# easyeda_source_code.net
KiCad netlist of a schematic drawn in EasyEDA
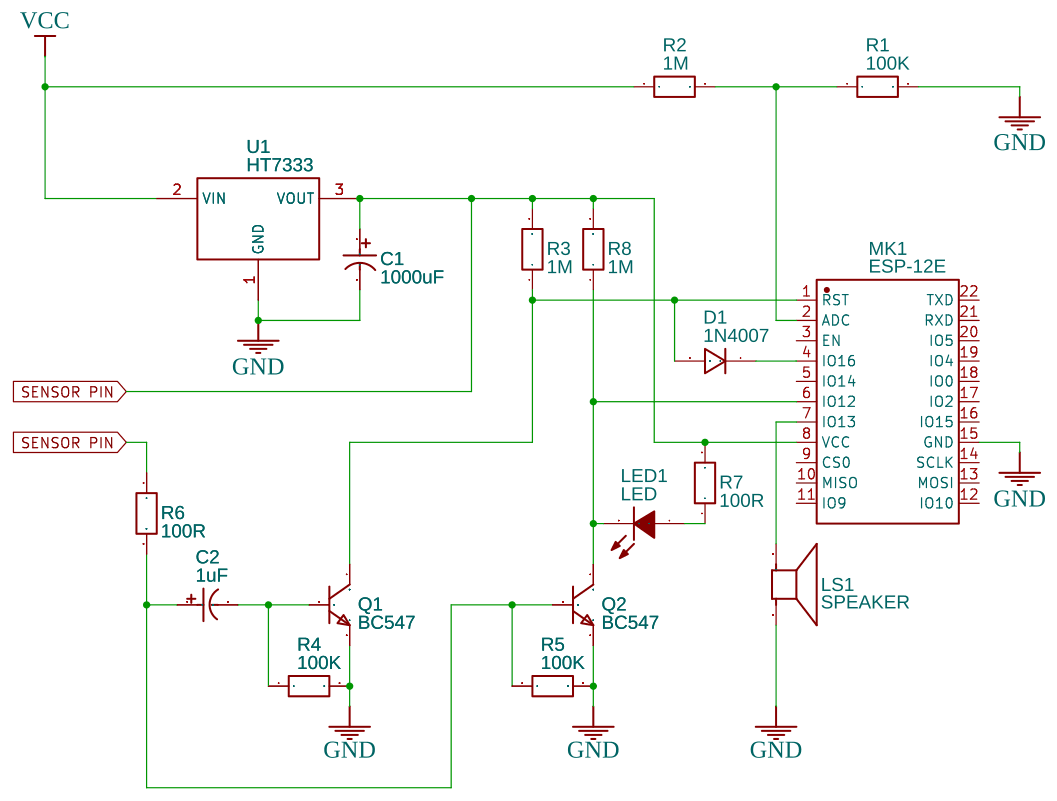
[diagram p0: schematic sheet]

(export (version "E")
  (design (tool "Eeschema 10.0.6"))
  (components
    (comp (ref "C1")
      (value "1000uF")
      (fields
        (field (name "BOM_Manufacturer Part") "1000uF 10V绿金 10*15")
        (field (name "BOM_Supplier Part") "C43339")
      )
      (libsource (lib "") (part "1000uF 10V 10*15"))
    )
    (comp (ref "C2")
      (value "1uF")
      (fields
        (field (name "BOM_Manufacturer Part") "1000uF 10V绿金 10*15")
        (field (name "BOM_Supplier Part") "C43339")
      )
      (libsource (lib "") (part "1000uF 10V 10*15_1"))
    )
    (comp (ref "D1")
      (value "1N4007")
      (fields (field (name "BOM_Manufacturer Part") "1N4007W") (field (name "BOM_Supplier Part") "C328592"))
      (libsource (lib "") (part "1N4007W"))
    )
    (comp (ref "LED1")
      (value "LED")
      (fields
        (field (name "BOM_Manufacturer Part") "19-217/R6C-AL1M2VY/3T")
        (field (name "BOM_Supplier Part") "C72044")
      )
      (libsource (lib "") (part "LED-0603_R"))
    )
    (comp (ref "LS1") (value "SPEAKER") (libsource (lib "") (part "SPEAKERPS12")))
    (comp (ref "MK1")
      (value "ESP-12E")
      (fields (field (name "BOM_Supplier Part") "C89297"))
      (libsource (lib "") (part "ESP-12E"))
    )
    (comp (ref "Q1")
      (value "BC547")
      (fields (field (name "BOM_Manufacturer Part") "BC547BTA") (field (name "BOM_Supplier Part") "C258144"))
      (libsource (lib "") (part "BC547BTA"))
    )
    (comp (ref "Q2")
      (value "BC547")
      (fields (field (name "BOM_Manufacturer Part") "BC547BTA") (field (name "BOM_Supplier Part") "C258144"))
      (libsource (lib "") (part "BC547BTA"))
    )
    (comp (ref "R1") (value "100K") (libsource (lib "") (part "R_0201_EU_1")))
    (comp (ref "R2") (value "1M") (libsource (lib "") (part "R_0201_EU_1")))
    (comp (ref "R3") (value "1M") (libsource (lib "") (part "R_0201_EU")))
    (comp (ref "R4") (value "100K") (libsource (lib "") (part "R_0201_EU_1")))
    (comp (ref "R5") (value "100K") (libsource (lib "") (part "R_0201_EU_1")))
    (comp (ref "R6") (value "100R") (libsource (lib "") (part "R_0201_EU_2")))
    (comp (ref "R7") (value "100R") (libsource (lib "") (part "R_0201_EU")))
    (comp (ref "R8") (value "1M") (libsource (lib "") (part "R_0201_EU")))
    (comp (ref "U1")
      (value "HT7333")
      (fields (field (name "BOM_Manufacturer Part") "HT7333-A") (field (name "BOM_Supplier Part") "C73726"))
      (libsource (lib "") (part "HT7333-A_C73726"))
    )
  )
  (nets
    (net (code "1") (name "GND") (class "Default")
      (node (ref "C1") (pin "2") (pinfunction "2_2") (pintype "input"))
      (node (ref "LS1") (pin "P$2") (pinfunction "-_P$2") (pintype "unspecified"))
      (node (ref "MK1") (pin "15") (pinfunction "GND_15") (pintype "unspecified"))
      (node (ref "Q1") (pin "3") (pinfunction "E_3") (pintype "unspecified"))
      (node (ref "Q2") (pin "3") (pinfunction "E_3") (pintype "unspecified"))
      (node (ref "R1") (pin "2") (pinfunction "2_2") (pintype "unspecified"))
      (node (ref "R4") (pin "2") (pinfunction "2_2") (pintype "unspecified"))
      (node (ref "R5") (pin "2") (pinfunction "2_2") (pintype "unspecified"))
      (node (ref "U1") (pin "1") (pinfunction "GND_1") (pintype "unspecified"))
    )
    (net (code "2") (name "Net-(LED1-Pad1)") (class "Default")
      (node (ref "LED1") (pin "1") (pinfunction "1_1") (pintype "unspecified"))
      (node (ref "R7") (pin "1") (pinfunction "1_1") (pintype "unspecified"))
    )
    (net (code "3") (name "Net-(LS1-+)") (class "Default")
      (node (ref "LS1") (pin "P$1") (pinfunction "+_P$1") (pintype "unspecified"))
      (node (ref "MK1") (pin "7") (pinfunction "IO13_7") (pintype "unspecified"))
    )
    (net (code "4") (name "Net-(MK1-ADC)") (class "Default")
      (node (ref "MK1") (pin "2") (pinfunction "ADC_2") (pintype "unspecified"))
      (node (ref "R1") (pin "1") (pinfunction "1_1") (pintype "unspecified"))
      (node (ref "R2") (pin "2") (pinfunction "2_2") (pintype "unspecified"))
    )
    (net (code "5") (name "Net-(MK1-IO12)") (class "Default")
      (node (ref "LED1") (pin "2") (pinfunction "2_2") (pintype "unspecified"))
      (node (ref "MK1") (pin "6") (pinfunction "IO12_6") (pintype "unspecified"))
      (node (ref "Q2") (pin "1") (pinfunction "C_1") (pintype "unspecified"))
      (node (ref "R8") (pin "1") (pinfunction "1_1") (pintype "unspecified"))
    )
    (net (code "6") (name "Net-(MK1-IO16)") (class "Default")
      (node (ref "D1") (pin "1") (pinfunction "1_1") (pintype "unspecified"))
      (node (ref "MK1") (pin "4") (pinfunction "IO16_4") (pintype "unspecified"))
    )
    (net (code "7") (name "Net-(MK1-RST)") (class "Default")
      (node (ref "D1") (pin "2") (pinfunction "2_2") (pintype "unspecified"))
      (node (ref "MK1") (pin "1") (pinfunction "RST_1") (pintype "unspecified"))
      (node (ref "Q1") (pin "1") (pinfunction "C_1") (pintype "unspecified"))
      (node (ref "R3") (pin "1") (pinfunction "1_1") (pintype "unspecified"))
    )
    (net (code "8") (name "Net-(Q1-B)") (class "Default")
      (node (ref "C2") (pin "2") (pinfunction "2_2") (pintype "input"))
      (node (ref "Q1") (pin "2") (pinfunction "B_2") (pintype "unspecified"))
      (node (ref "R4") (pin "1") (pinfunction "1_1") (pintype "unspecified"))
    )
    (net (code "9") (name "Net-(Q2-B)") (class "Default")
      (node (ref "C2") (pin "1") (pinfunction "1_1") (pintype "input"))
      (node (ref "Q2") (pin "2") (pinfunction "B_2") (pintype "unspecified"))
      (node (ref "R5") (pin "1") (pinfunction "1_1") (pintype "unspecified"))
      (node (ref "R6") (pin "2") (pinfunction "2_2") (pintype "unspecified"))
    )
    (net (code "10") (name "SENSOR PIN") (class "Default")
      (node (ref "C1") (pin "1") (pinfunction "1_1") (pintype "input"))
      (node (ref "MK1") (pin "8") (pinfunction "VCC_8") (pintype "unspecified"))
      (node (ref "R3") (pin "2") (pinfunction "2_2") (pintype "unspecified"))
      (node (ref "R6") (pin "1") (pinfunction "1_1") (pintype "unspecified"))
      (node (ref "R7") (pin "2") (pinfunction "2_2") (pintype "unspecified"))
      (node (ref "R8") (pin "2") (pinfunction "2_2") (pintype "unspecified"))
      (node (ref "U1") (pin "3") (pinfunction "VOUT_3") (pintype "unspecified"))
    )
    (net (code "11") (name "VCC") (class "Default")
      (node (ref "R2") (pin "1") (pinfunction "1_1") (pintype "unspecified"))
      (node (ref "U1") (pin "2") (pinfunction "VIN_2") (pintype "unspecified"))
    )
    (net (code "12") (name "unconnected-(MK1-CS0-Pad9)") (class "Default")
      (node (ref "MK1") (pin "9") (pinfunction "CS0_9") (pintype "unspecified"))
    )
    (net (code "13") (name "unconnected-(MK1-EN-Pad3)") (class "Default")
      (node (ref "MK1") (pin "3") (pinfunction "EN_3") (pintype "unspecified"))
    )
    (net (code "14") (name "unconnected-(MK1-IO0-Pad18)") (class "Default")
      (node (ref "MK1") (pin "18") (pinfunction "IO0_18") (pintype "unspecified"))
    )
    (net (code "15") (name "unconnected-(MK1-IO2-Pad17)") (class "Default")
      (node (ref "MK1") (pin "17") (pinfunction "IO2_17") (pintype "unspecified"))
    )
    (net (code "16") (name "unconnected-(MK1-IO4-Pad19)") (class "Default")
      (node (ref "MK1") (pin "19") (pinfunction "IO4_19") (pintype "unspecified"))
    )
    (net (code "17") (name "unconnected-(MK1-IO5-Pad20)") (class "Default")
      (node (ref "MK1") (pin "20") (pinfunction "IO5_20") (pintype "unspecified"))
    )
    (net (code "18") (name "unconnected-(MK1-IO9-Pad11)") (class "Default")
      (node (ref "MK1") (pin "11") (pinfunction "IO9_11") (pintype "unspecified"))
    )
    (net (code "19") (name "unconnected-(MK1-IO10-Pad12)") (class "Default")
      (node (ref "MK1") (pin "12") (pinfunction "IO10_12") (pintype "unspecified"))
    )
    (net (code "20") (name "unconnected-(MK1-IO14-Pad5)") (class "Default")
      (node (ref "MK1") (pin "5") (pinfunction "IO14_5") (pintype "unspecified"))
    )
    (net (code "21") (name "unconnected-(MK1-IO15-Pad16)") (class "Default")
      (node (ref "MK1") (pin "16") (pinfunction "IO15_16") (pintype "unspecified"))
    )
    (net (code "22") (name "unconnected-(MK1-MISO-Pad10)") (class "Default")
      (node (ref "MK1") (pin "10") (pinfunction "MISO_10") (pintype "unspecified"))
    )
    (net (code "23") (name "unconnected-(MK1-MOSI-Pad13)") (class "Default")
      (node (ref "MK1") (pin "13") (pinfunction "MOSI_13") (pintype "unspecified"))
    )
    (net (code "24") (name "unconnected-(MK1-RXD-Pad21)") (class "Default")
      (node (ref "MK1") (pin "21") (pinfunction "RXD_21") (pintype "unspecified"))
    )
    (net (code "25") (name "unconnected-(MK1-SCLK-Pad14)") (class "Default")
      (node (ref "MK1") (pin "14") (pinfunction "SCLK_14") (pintype "unspecified"))
    )
    (net (code "26") (name "unconnected-(MK1-TXD-Pad22)") (class "Default")
      (node (ref "MK1") (pin "22") (pinfunction "TXD_22") (pintype "unspecified"))
    )
  )
)
